# Power.net
KiCad netlist of a schematic drawn in Altium Designer
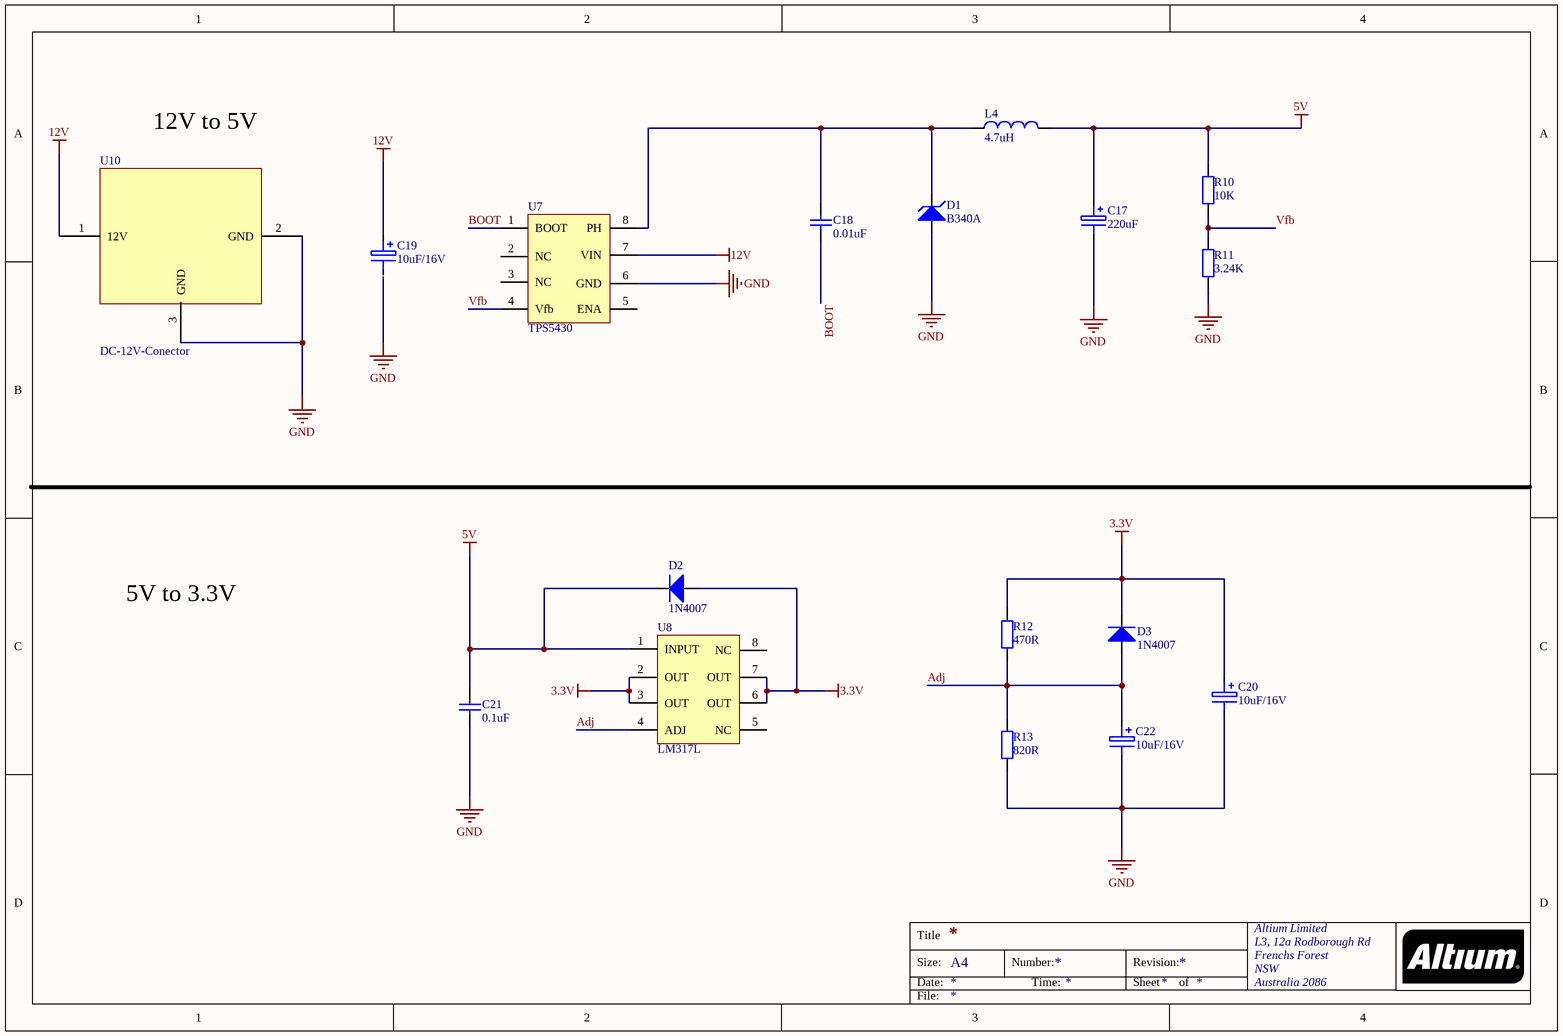
[diagram p0: Power.SchDoc]

(export (version "E")
  (design (tool "Eeschema 10.0.6"))
  (components
    (comp (ref "C17")
      (value "220uF")
      (footprint "CAPM-7.0*4.5")
      (description "aluminum")
      (libsource (lib "ToponLib") (part "Cap3"))
    )
    (comp (ref "C18")
      (value "0.01uF")
      (footprint "0603")
      (description "ceramic")
      (libsource (lib "ToponLib") (part "Cap1"))
    )
    (comp (ref "C19")
      (value "10uF/16V")
      (footprint "CAPM-7.0*4.5")
      (description "aluminum")
      (libsource (lib "ToponLib") (part "Cap3"))
    )
    (comp (ref "C20")
      (value "10uF/16V")
      (footprint "CAPM-5.5*3.3")
      (description "aluminum")
      (libsource (lib "ToponLib") (part "Cap3"))
    )
    (comp (ref "C21")
      (value "0.1uF")
      (footprint "0603")
      (description "ceramic")
      (libsource (lib "ToponLib") (part "Cap1"))
    )
    (comp (ref "C22")
      (value "10uF/16V")
      (footprint "CAPM-5.5*3.3")
      (description "aluminum")
      (libsource (lib "ToponLib") (part "Cap3"))
    )
    (comp (ref "D1") (value "B340A") (footprint "DO214-AC") (libsource (lib "ToponLib") (part "B340A-13-F")))
    (comp (ref "D2") (value "1N4007") (footprint "DO214-AC") (libsource (lib "ToponLib") (part "1N4007")))
    (comp (ref "D3") (value "1N4007") (footprint "DO214-AC") (libsource (lib "ToponLib") (part "1N4007")))
    (comp (ref "L4") (value "4.7uH") (footprint "7*7*4-15uH") (libsource (lib "ToponLib") (part "Inductor")))
    (comp (ref "R10") (value "10K") (footprint "0603") (libsource (lib "ToponLib") (part "Res")))
    (comp (ref "R11") (value "3.24K") (footprint "0603") (libsource (lib "ToponLib") (part "Res")))
    (comp (ref "R12") (value "470R") (footprint "0603") (libsource (lib "ToponLib") (part "Res")))
    (comp (ref "R13") (value "820R") (footprint "0603") (libsource (lib "ToponLib") (part "Res")))
    (comp (ref "U7") (value "TPS5430") (footprint "TPS5430") (libsource (lib "ToponLib") (part "TPS5430")))
    (comp (ref "U8") (value "LM317L") (footprint "LM317L") (libsource (lib "ToponLib") (part "LM317L")))
    (comp (ref "U10")
      (value "DC-12V-Conector")
      (footprint "DC-12V-Con")
      (libsource (lib "ToponLib") (part "DC12V-Connector"))
    )
  )
  (nets
    (net (code "1") (name "/Adj") (class "Default")
      (node (ref "C22") (pin "1") (pinfunction "1_1") (pintype "passive"))
      (node (ref "D3") (pin "1") (pinfunction "A_1") (pintype "passive"))
      (node (ref "R12") (pin "1") (pinfunction "1_1") (pintype "passive"))
      (node (ref "R13") (pin "2") (pinfunction "2_2") (pintype "passive"))
      (node (ref "U8") (pin "4") (pinfunction "ADJ_4") (pintype "passive"))
    )
    (net (code "2") (name "/BOOT") (class "Default")
      (node (ref "C18") (pin "1") (pinfunction "1_1") (pintype "passive"))
      (node (ref "U7") (pin "1") (pinfunction "BOOT_1") (pintype "passive"))
    )
    (net (code "3") (name "/Vfb") (class "Default")
      (node (ref "R10") (pin "1") (pinfunction "1_1") (pintype "passive"))
      (node (ref "R11") (pin "2") (pinfunction "2_2") (pintype "passive"))
      (node (ref "U7") (pin "4") (pinfunction "Vfb_4") (pintype "passive"))
    )
    (net (code "4") (name "3.3V") (class "Default")
      (node (ref "C20") (pin "1") (pinfunction "1_1") (pintype "passive"))
      (node (ref "D2") (pin "1") (pinfunction "A_1") (pintype "passive"))
      (node (ref "D3") (pin "2") (pinfunction "K_2") (pintype "passive"))
      (node (ref "R12") (pin "2") (pinfunction "2_2") (pintype "passive"))
      (node (ref "U8") (pin "2") (pinfunction "OUT_2") (pintype "passive"))
      (node (ref "U8") (pin "3") (pinfunction "OUT_3") (pintype "passive"))
      (node (ref "U8") (pin "6") (pinfunction "OUT_6") (pintype "passive"))
      (node (ref "U8") (pin "7") (pinfunction "OUT_7") (pintype "passive"))
    )
    (net (code "5") (name "5V") (class "Default")
      (node (ref "C17") (pin "1") (pinfunction "1_1") (pintype "passive"))
      (node (ref "C21") (pin "2") (pinfunction "2_2") (pintype "passive"))
      (node (ref "D2") (pin "2") (pinfunction "K_2") (pintype "passive"))
      (node (ref "L4") (pin "2") (pinfunction "2_2") (pintype "passive"))
      (node (ref "R10") (pin "2") (pinfunction "2_2") (pintype "passive"))
      (node (ref "U8") (pin "1") (pinfunction "INPUT_1") (pintype "passive"))
    )
    (net (code "6") (name "12V") (class "Default")
      (node (ref "C19") (pin "1") (pinfunction "1_1") (pintype "passive"))
      (node (ref "U10") (pin "1") (pinfunction "12V_1") (pintype "passive"))
      (node (ref "U7") (pin "7") (pinfunction "VIN_7") (pintype "passive"))
    )
    (net (code "7") (name "GND") (class "Default")
      (node (ref "C17") (pin "2") (pinfunction "2_2") (pintype "passive"))
      (node (ref "C20") (pin "2") (pinfunction "2_2") (pintype "passive"))
      (node (ref "C21") (pin "1") (pinfunction "1_1") (pintype "passive"))
      (node (ref "C22") (pin "2") (pinfunction "2_2") (pintype "passive"))
      (node (ref "D1") (pin "1") (pinfunction "A_1") (pintype "passive"))
      (node (ref "R11") (pin "1") (pinfunction "1_1") (pintype "passive"))
      (node (ref "R13") (pin "1") (pinfunction "1_1") (pintype "passive"))
      (node (ref "U10") (pin "2") (pinfunction "GND_2") (pintype "passive"))
      (node (ref "U10") (pin "3") (pinfunction "GND_3") (pintype "passive"))
      (node (ref "U7") (pin "6") (pinfunction "GND_6") (pintype "passive"))
    )
    (net (code "8") (name "Net-(D1-K)") (class "Default")
      (node (ref "C18") (pin "2") (pinfunction "2_2") (pintype "passive"))
      (node (ref "D1") (pin "2") (pinfunction "K_2") (pintype "passive"))
      (node (ref "L4") (pin "1") (pinfunction "1_1") (pintype "passive"))
      (node (ref "U7") (pin "8") (pinfunction "PH_8") (pintype "passive"))
    )
    (net (code "9") (name "unconnected-(C19-Pad2)") (class "Default")
      (node (ref "C19") (pin "2") (pinfunction "2_2") (pintype "passive"))
    )
    (net (code "10") (name "unconnected-(U7-ENA-Pad5)") (class "Default")
      (node (ref "U7") (pin "5") (pinfunction "ENA_5") (pintype "passive"))
    )
    (net (code "11") (name "unconnected-(U7-NC-Pad2)") (class "Default")
      (node (ref "U7") (pin "2") (pinfunction "NC_2") (pintype "passive"))
    )
    (net (code "12") (name "unconnected-(U7-NC-Pad3)") (class "Default")
      (node (ref "U7") (pin "3") (pinfunction "NC_3") (pintype "passive"))
    )
    (net (code "13") (name "unconnected-(U8-NC-Pad5)") (class "Default")
      (node (ref "U8") (pin "5") (pinfunction "NC_5") (pintype "passive"))
    )
    (net (code "14") (name "unconnected-(U8-NC-Pad8)") (class "Default")
      (node (ref "U8") (pin "8") (pinfunction "NC_8") (pintype "passive"))
    )
  )
)
